# ActiTouch.net
KiCad netlist of a schematic drawn in Altium Designer
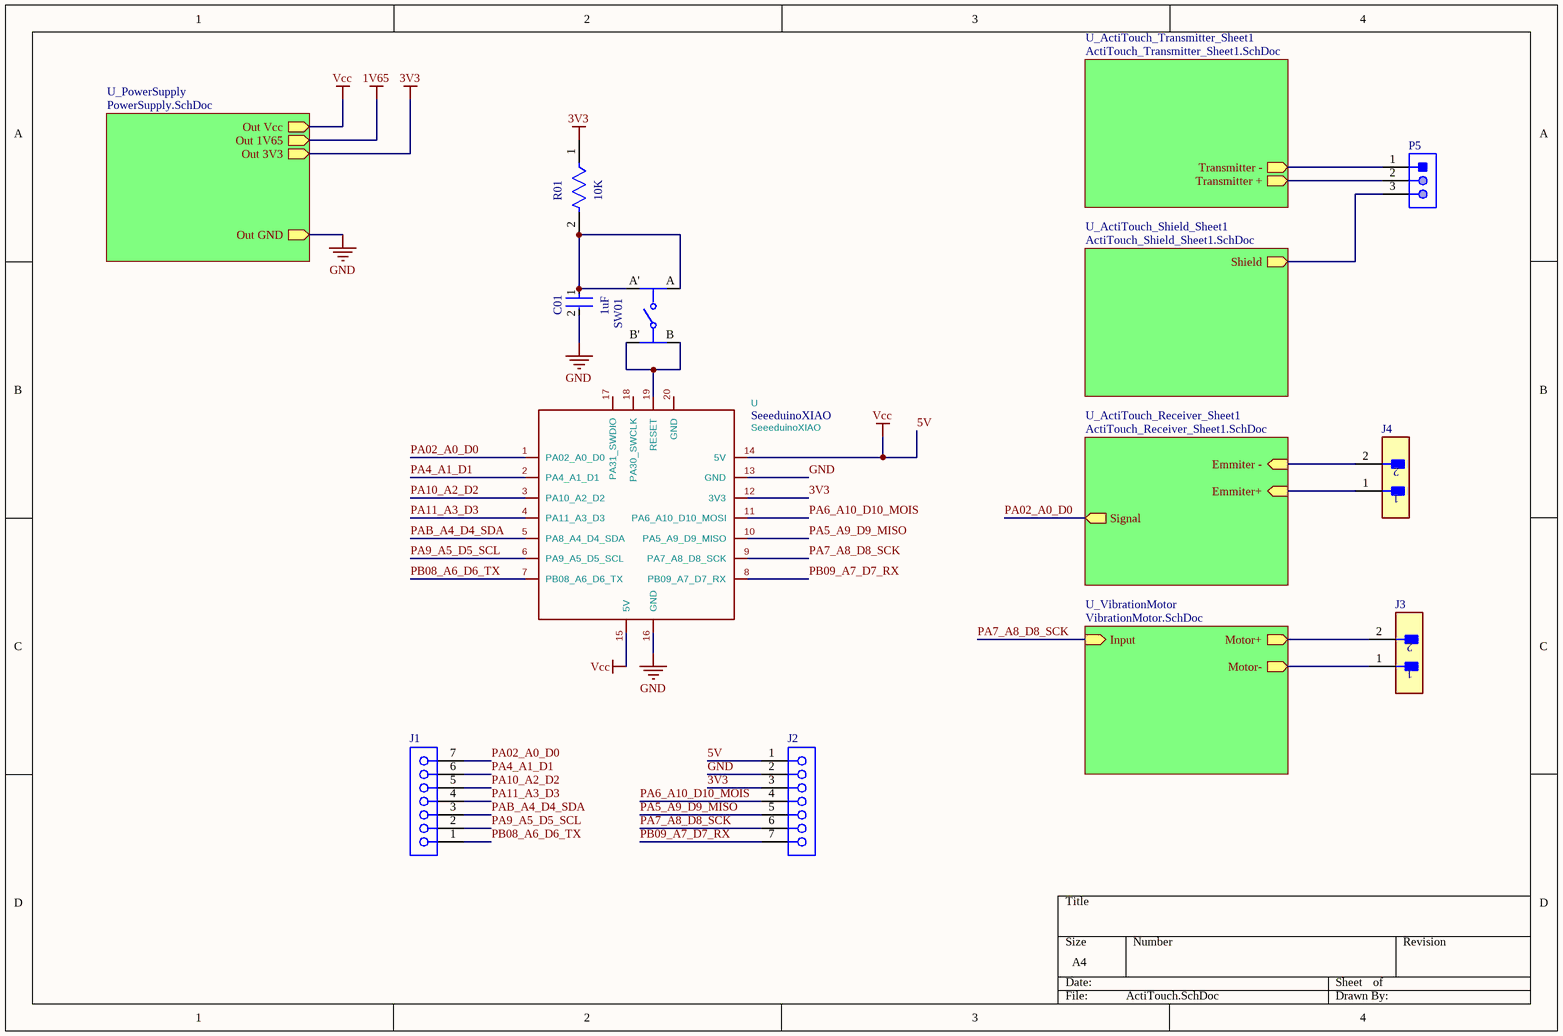
[diagram p0: ActiTouch.SchDoc]

(export (version "E")
  (design (tool "Eeschema 10.0.6"))
  (components
    (comp (ref "C01")
      (value "1uF")
      (footprint "FP-0603-L_1_6_0_15-W_0_81-IPC_A")
      (description "General Purpose Ceramic Capacitor, 0603, 1uF, 10%, X5R, 15%, 10V")
      (fields (field (name "TOLERANCE") "10%") (field (name "VOLTAGE") "10V"))
      (libsource (lib "Altium Content Vault") (part "02cd4be3c70576c341d710602a673aa"))
    )
    (comp (ref "J1")
      (value "SSQ-107-01-G-S")
      (footprint "SMTC-SSQ-107-01-X-S")
      (description "SQ Post Socket, Through-hole, Vertical, -55 to 125 degC, 2.54 mm Pitch, 7-Pin, Female, RoHS")
      (fields (field (name "MANUFACTURER") "Samtec"))
      (libsource (lib "Altium Content Vault") (part "SMTC-SSQ-107-01-X-S"))
    )
    (comp (ref "J2")
      (value "SSQ-107-01-G-S")
      (footprint "SMTC-SSQ-107-01-X-S")
      (description "SQ Post Socket, Through-hole, Vertical, -55 to 125 degC, 2.54 mm Pitch, 7-Pin, Female, RoHS")
      (fields (field (name "MANUFACTURER") "Samtec"))
      (libsource (lib "Altium Content Vault") (part "SMTC-SSQ-107-01-X-S"))
    )
    (comp (ref "J3")
      (value "GRPB021VWVN-RC")
      (footprint "FP-GRPB021VWVN-RC-MFG")
      (description "CONN HEADER VERT 2POS 1.27MM")
      (libsource (lib "Altium Content Vault") (part "3bc925449376181038e59eaffc5286c"))
    )
    (comp (ref "J4")
      (value "GRPB021VWVN-RC")
      (footprint "FP-GRPB021VWVN-RC-MFG")
      (description "CONN HEADER VERT 2POS 1.27MM")
      (libsource (lib "Altium Content Vault") (part "3bc925449376181038e59eaffc5286c"))
    )
    (comp (ref "P5")
      (value "GRPB031VWVN-RC")
      (footprint "SLIN-GRPB031VWVN-RC_V")
      (fields (field (name "MANUFACTURER") "Sullins"))
      (libsource (lib "Altium Content Vault") (part "CN-1P-M-R3"))
    )
    (comp (ref "R01")
      (value "10K")
      (footprint "FP-RNCP0603-MFG")
      (description "12.4kΩ ±1% 0.125W 0603 High Power Anti-Sulfur Thin Film Chip Resistor")
      (fields (field (name "TOLERANCE") "1%"))
      (libsource (lib "Altium Content Vault") (part "1029c3af85768c4190bb7ad29bc67b5"))
    )
    (comp (ref "SW01")
      (value "EVPAF7B70")
      (footprint "FP-EVPAF7B70-MFG")
      (description "SWITCH TACTILE SPST-NO 0.02A 15V")
      (libsource (lib "Altium Content Vault") (part "b7ac77db5a7e9d2071bd1db0bb096f6"))
    )
    (comp (ref "U")
      (value "SeeeduinoXIAO")
      (footprint "Seeeduino XIAO-MOUDLE14P-2.54-21X17.8MM")
      (fields (field (name "ALTIUM_VALUE") "SeeeduinoXIAO"))
      (libsource (lib "Seeeduino XIAO") (part "SeeeduinoXIAO"))
    )
  )
  (nets
    (net (code "1") (name "/Emmiter -") (class "Default")
      (node (ref "J4") (pin "2") (pinfunction "2_2") (pintype "passive"))
    )
    (net (code "2") (name "/Emmiter+") (class "Default")
      (node (ref "J4") (pin "1") (pinfunction "1_1") (pintype "passive"))
    )
    (net (code "3") (name "/Motor+") (class "Default")
      (node (ref "J3") (pin "2") (pinfunction "2_2") (pintype "passive"))
    )
    (net (code "4") (name "/Motor-") (class "Default")
      (node (ref "J3") (pin "1") (pinfunction "1_1") (pintype "passive"))
    )
    (net (code "5") (name "/PA02_A0_D0") (class "Default")
      (node (ref "J1") (pin "7") (pinfunction "7_7") (pintype "passive"))
      (node (ref "U") (pin "1") (pinfunction "PA02_A0_D0_1") (pintype "passive"))
    )
    (net (code "6") (name "/PA4_A1_D1") (class "Default")
      (node (ref "J1") (pin "6") (pinfunction "6_6") (pintype "passive"))
      (node (ref "U") (pin "2") (pinfunction "PA4_A1_D1_2") (pintype "passive"))
    )
    (net (code "7") (name "/PA5_A9_D9_MISO") (class "Default")
      (node (ref "J2") (pin "5") (pinfunction "5_5") (pintype "passive"))
      (node (ref "U") (pin "10") (pinfunction "PA5_A9_D9_MISO_10") (pintype "passive"))
    )
    (net (code "8") (name "/PA6_A10_D10_MOIS") (class "Default")
      (node (ref "J2") (pin "4") (pinfunction "4_4") (pintype "passive"))
      (node (ref "U") (pin "11") (pinfunction "PA6_A10_D10_MOSI_11") (pintype "passive"))
    )
    (net (code "9") (name "/PA7_A8_D8_SCK") (class "Default")
      (node (ref "J2") (pin "6") (pinfunction "6_6") (pintype "passive"))
      (node (ref "U") (pin "9") (pinfunction "PA7_A8_D8_SCK_9") (pintype "passive"))
    )
    (net (code "10") (name "/PA9_A5_D5_SCL") (class "Default")
      (node (ref "J1") (pin "2") (pinfunction "2_2") (pintype "passive"))
      (node (ref "U") (pin "6") (pinfunction "PA9_A5_D5_SCL_6") (pintype "passive"))
    )
    (net (code "11") (name "/PA10_A2_D2") (class "Default")
      (node (ref "J1") (pin "5") (pinfunction "5_5") (pintype "passive"))
      (node (ref "U") (pin "3") (pinfunction "PA10_A2_D2_3") (pintype "passive"))
    )
    (net (code "12") (name "/PA11_A3_D3") (class "Default")
      (node (ref "J1") (pin "4") (pinfunction "4_4") (pintype "passive"))
      (node (ref "U") (pin "4") (pinfunction "PA11_A3_D3_4") (pintype "passive"))
    )
    (net (code "13") (name "/PAB_A4_D4_SDA") (class "Default")
      (node (ref "J1") (pin "3") (pinfunction "3_3") (pintype "passive"))
      (node (ref "U") (pin "5") (pinfunction "PA8_A4_D4_SDA_5") (pintype "passive"))
    )
    (net (code "14") (name "/PB08_A6_D6_TX") (class "Default")
      (node (ref "J1") (pin "1") (pinfunction "1_1") (pintype "passive"))
      (node (ref "U") (pin "7") (pinfunction "PB08_A6_D6_TX_7") (pintype "passive"))
    )
    (net (code "15") (name "/PB09_A7_D7_RX") (class "Default")
      (node (ref "J2") (pin "7") (pinfunction "7_7") (pintype "passive"))
      (node (ref "U") (pin "8") (pinfunction "PB09_A7_D7_RX_8") (pintype "passive"))
    )
    (net (code "16") (name "/Shield") (class "Default")
      (node (ref "P5") (pin "3") (pinfunction "3_3") (pintype "passive"))
    )
    (net (code "17") (name "/Transmitter +") (class "Default")
      (node (ref "P5") (pin "2") (pinfunction "2_2") (pintype "passive"))
    )
    (net (code "18") (name "/Transmitter -") (class "Default")
      (node (ref "P5") (pin "1") (pinfunction "1_1") (pintype "passive"))
    )
    (net (code "20") (name "3V3") (class "Default")
      (node (ref "J2") (pin "3") (pinfunction "3_3") (pintype "passive"))
      (node (ref "R01") (pin "1") (pinfunction "1_1") (pintype "passive"))
      (node (ref "U") (pin "12") (pinfunction "3V3_12") (pintype "passive"))
    )
    (net (code "21") (name "GND") (class "Default")
      (node (ref "C01") (pin "2") (pinfunction "2_2") (pintype "passive"))
      (node (ref "J2") (pin "2") (pinfunction "2_2") (pintype "passive"))
      (node (ref "U") (pin "13") (pinfunction "GND_13") (pintype "passive"))
      (node (ref "U") (pin "16") (pinfunction "GND_16") (pintype "passive"))
    )
    (net (code "22") (name "Net-(C01-Pad1)") (class "Default")
      (node (ref "C01") (pin "1") (pinfunction "1_1") (pintype "passive"))
      (node (ref "R01") (pin "2") (pinfunction "2_2") (pintype "passive"))
      (node (ref "SW01") (pin "A") (pinfunction "A_A") (pintype "passive"))
      (node (ref "SW01") (pin "A'") (pinfunction "A'_A'") (pintype "passive"))
    )
    (net (code "23") (name "Net-(U-RESET)") (class "Default")
      (node (ref "SW01") (pin "B") (pinfunction "B_B") (pintype "passive"))
      (node (ref "SW01") (pin "B'") (pinfunction "B'_B'") (pintype "passive"))
      (node (ref "U") (pin "19") (pinfunction "RESET_19") (pintype "passive"))
    )
    (net (code "24") (name "Vcc") (class "Default")
      (node (ref "J2") (pin "1") (pinfunction "1_1") (pintype "passive"))
      (node (ref "U") (pin "14") (pinfunction "5V_14") (pintype "passive"))
      (node (ref "U") (pin "15") (pinfunction "5V_15") (pintype "passive"))
    )
    (net (code "25") (name "unconnected-(U-GND-Pad20)") (class "Default")
      (node (ref "U") (pin "20") (pinfunction "GND_20") (pintype "passive"))
    )
    (net (code "26") (name "unconnected-(U-PA30_SWCLK-Pad18)") (class "Default")
      (node (ref "U") (pin "18") (pinfunction "PA30_SWCLK_18") (pintype "passive"))
    )
    (net (code "27") (name "unconnected-(U-PA31_SWDIO-Pad17)") (class "Default")
      (node (ref "U") (pin "17") (pinfunction "PA31_SWDIO_17") (pintype "passive"))
    )
  )
)
